# receiver_mp3.net
KiCad netlist of a schematic drawn in EAGLE
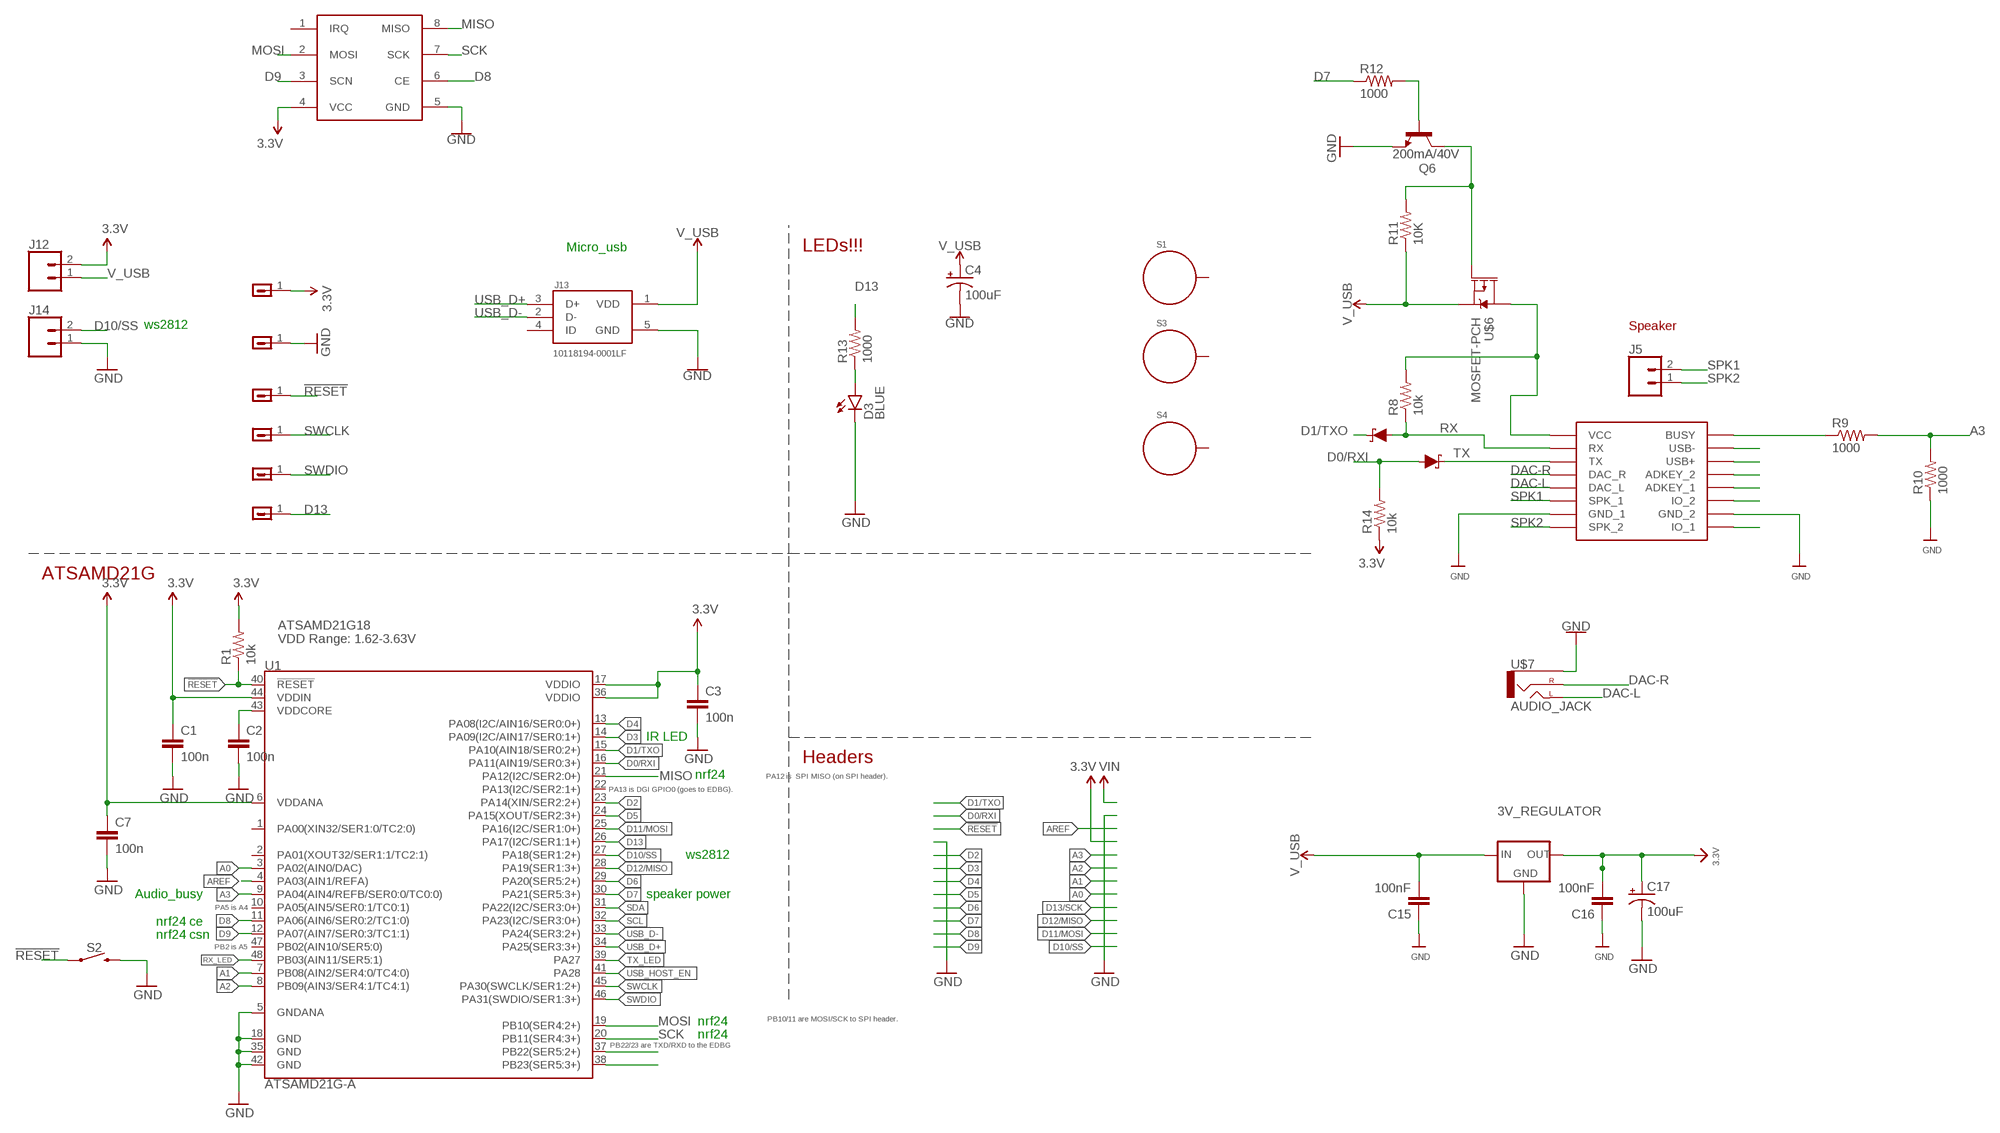
[diagram p0: schematic, sheet 1]

(export (version "E")
  (design (tool "Eeschema 10.0.6"))
  (components
    (comp (ref "3V_REGULATOR")
      (value "LDL1117_5V_REG")
      (footprint "eagle-import:SOT223")
      (libsource (lib "eagle-import") (part "LDL1117_5V_REG"))
    )
    (comp (ref "C1")
      (value "100n")
      (footprint "eagle-import:0805")
      (libsource (lib "eagle-import") (part "CAP0805"))
    )
    (comp (ref "C2")
      (value "100n")
      (footprint "eagle-import:0805")
      (libsource (lib "eagle-import") (part "CAP0805"))
    )
    (comp (ref "C3")
      (value "100n")
      (footprint "eagle-import:0805")
      (libsource (lib "eagle-import") (part "CAP0805"))
    )
    (comp (ref "C4")
      (value "100uF")
      (footprint "eagle-import:CPOL-RADIAL-2.5MM-6.5MM")
      (libsource (lib "eagle-import") (part "100UF-POLAR-RADIAL-2.5MM-25V-20%"))
    )
    (comp (ref "C7")
      (value "100n")
      (footprint "eagle-import:0805")
      (libsource (lib "eagle-import") (part "CAP0805"))
    )
    (comp (ref "C15")
      (value "100nF")
      (footprint "eagle-import:0805")
      (libsource (lib "eagle-import") (part "10UF-0805-10V-10%"))
    )
    (comp (ref "C16")
      (value "100nF")
      (footprint "eagle-import:0805")
      (libsource (lib "eagle-import") (part "10UF-0805-10V-10%"))
    )
    (comp (ref "C17")
      (value "100uF")
      (footprint "eagle-import:CPOL-RADIAL-2.5MM-6.5MM")
      (libsource (lib "eagle-import") (part "100UF-POLAR-RADIAL-2.5MM-25V-20%"))
    )
    (comp (ref "D1")
      (value "3A/40V/500mV")
      (footprint "eagle-import:SMA-DIODE")
      (libsource (lib "eagle-import") (part "DIODE-SCHOTTKY-B340A"))
    )
    (comp (ref "D3")
      (value "BLUE")
      (footprint "eagle-import:LED-1206")
      (libsource (lib "eagle-import") (part "LED-BLUE1206"))
    )
    (comp (ref "D5")
      (value "3A/40V/500mV")
      (footprint "eagle-import:SMA-DIODE")
      (libsource (lib "eagle-import") (part "DIODE-SCHOTTKY-B340A"))
    )
    (comp (ref "J5")
      (value "CONN_025MM")
      (footprint "eagle-import:SCREWTERMINAL-5MM-2")
      (libsource (lib "eagle-import") (part "CONN_025MM"))
    )
    (comp (ref "J12")
      (value "CONN_025MM")
      (footprint "eagle-import:SCREWTERMINAL-5MM-2")
      (libsource (lib "eagle-import") (part "CONN_025MM"))
    )
    (comp (ref "J13")
      (value "10118194-0001LF")
      (footprint "eagle-import:FRAMATOME_10118194-0001LF")
      (fields (field (name "MF") "Amphenol ICC"))
      (libsource (lib "eagle-import") (part "10118194-0001LF"))
    )
    (comp (ref "J14")
      (value "CONN_025MM")
      (footprint "eagle-import:SCREWTERMINAL-5MM-2")
      (libsource (lib "eagle-import") (part "CONN_025MM"))
    )
    (comp (ref "Q6")
      (value "200mA/40V")
      (footprint "eagle-import:TO-92-EZ")
      (libsource (lib "eagle-import") (part "TRANS_NPN-2N3904-EZ"))
    )
    (comp (ref "R1")
      (value "10k")
      (footprint "eagle-import:0805")
      (libsource (lib "eagle-import") (part "RESISTOR0805-RES"))
    )
    (comp (ref "R8")
      (value "10k")
      (footprint "eagle-import:0805")
      (libsource (lib "eagle-import") (part "RESISTOR0805-RES"))
    )
    (comp (ref "R9")
      (value "1000")
      (footprint "eagle-import:0805")
      (libsource (lib "eagle-import") (part "SparkFun-Passives_RESISTOR0805-RES"))
    )
    (comp (ref "R10")
      (value "1000")
      (footprint "eagle-import:0805")
      (libsource (lib "eagle-import") (part "SparkFun-Passives_RESISTOR0805-RES"))
    )
    (comp (ref "R11")
      (value "10K")
      (footprint "eagle-import:0805")
      (libsource (lib "eagle-import") (part "SparkFun-Passives_RESISTOR0805-RES"))
    )
    (comp (ref "R12")
      (value "1000")
      (footprint "eagle-import:0805")
      (libsource (lib "eagle-import") (part "SparkFun-Passives_RESISTOR0805-RES"))
    )
    (comp (ref "R13")
      (value "1000")
      (footprint "eagle-import:0805")
      (libsource (lib "eagle-import") (part "SparkFun-Passives_RESISTOR0805-RES"))
    )
    (comp (ref "R14")
      (value "10k")
      (footprint "eagle-import:0805")
      (libsource (lib "eagle-import") (part "RESISTOR0805-RES"))
    )
    (comp (ref "S1")
      (value "STANDOFF_ELECTRICAL144")
      (footprint "eagle-import:STANDOFF_ELECTRICAL_144MILL_NORMAL_SCREW")
      (libsource (lib "eagle-import") (part "STANDOFF_ELECTRICAL144"))
    )
    (comp (ref "S2")
      (value "MOMENTARY-SWITCH-SPST-PTH-6.0MM-KIT")
      (footprint "eagle-import:TACTILE_SWITCH_PTH_6.0MM_KIT")
      (libsource (lib "eagle-import") (part "MOMENTARY-SWITCH-SPST-PTH-6.0MM-KIT"))
    )
    (comp (ref "S3")
      (value "STANDOFF_ELECTRICAL144")
      (footprint "eagle-import:STANDOFF_ELECTRICAL_144MILL_NORMAL_SCREW")
      (libsource (lib "eagle-import") (part "STANDOFF_ELECTRICAL144"))
    )
    (comp (ref "S4")
      (value "STANDOFF_ELECTRICAL144")
      (footprint "eagle-import:STANDOFF_ELECTRICAL_144MILL_NORMAL_SCREW")
      (libsource (lib "eagle-import") (part "STANDOFF_ELECTRICAL144"))
    )
    (comp (ref "U$1")
      (value "DFPLAYER")
      (footprint "eagle-import:DFPLAYER")
      (libsource (lib "eagle-import") (part "DFPLAYER"))
    )
    (comp (ref "U$3")
      (value "NRF24L01")
      (footprint "eagle-import:NRF24L01")
      (libsource (lib "eagle-import") (part "NRF24L01"))
    )
    (comp (ref "U$6")
      (value "MOSFET-PCH")
      (footprint "eagle-import:DPAK")
      (libsource (lib "eagle-import") (part "MOSFET-PCH"))
    )
    (comp (ref "U$7")
      (value "AUDIO_JACK")
      (footprint "eagle-import:1_8_AUDIO_JACK")
      (libsource (lib "eagle-import") (part "AUDIO_JACK"))
    )
    (comp (ref "U$8")
      (value "CONN_011.27MM")
      (footprint "eagle-import:1X01-1.27MM")
      (libsource (lib "eagle-import") (part "CONN_011.27MM"))
    )
    (comp (ref "U$13")
      (value "CONN_011.27MM")
      (footprint "eagle-import:1X01-1.27MM")
      (libsource (lib "eagle-import") (part "CONN_011.27MM"))
    )
    (comp (ref "U$18")
      (value "CONN_011.27MM")
      (footprint "eagle-import:1X01-1.27MM")
      (libsource (lib "eagle-import") (part "CONN_011.27MM"))
    )
    (comp (ref "U$19")
      (value "CONN_011.27MM")
      (footprint "eagle-import:1X01-1.27MM")
      (libsource (lib "eagle-import") (part "CONN_011.27MM"))
    )
    (comp (ref "U$20")
      (value "CONN_011.27MM")
      (footprint "eagle-import:1X01-1.27MM")
      (libsource (lib "eagle-import") (part "CONN_011.27MM"))
    )
    (comp (ref "U$22")
      (value "CONN_011.27MM")
      (footprint "eagle-import:1X01-1.27MM")
      (libsource (lib "eagle-import") (part "CONN_011.27MM"))
    )
    (comp (ref "U1")
      (value "ATSAMD21G-A")
      (footprint "eagle-import:TQFP-48")
      (libsource (lib "eagle-import") (part "ATSAMD21G-A"))
    )
  )
  (nets
    (net (code "1") (name "/DAC-L") (class "Default")
      (node (ref "U$1") (pin "DAC_L") (pinfunction "DAC_L_DAC_L") (pintype "bidirectional"))
      (node (ref "U$7") (pin "LEFT_TIP_1") (pinfunction "LEFT_LEFT_TIP_1") (pintype "bidirectional"))
    )
    (net (code "2") (name "/DAC-R") (class "Default")
      (node (ref "U$1") (pin "DAC_R") (pinfunction "DAC_R_DAC_R") (pintype "bidirectional"))
      (node (ref "U$7") (pin "RIGHT") (pinfunction "RIGHT_RIGHT") (pintype "bidirectional"))
    )
    (net (code "3") (name "/MISO") (class "Default")
      (node (ref "U$3") (pin "8") (pinfunction "MISO_8") (pintype "bidirectional"))
      (node (ref "U1") (pin "21") (pinfunction "PA12(I2C/SER2:0+)_21") (pintype "bidirectional"))
    )
    (net (code "4") (name "/MOSI") (class "Default")
      (node (ref "U$3") (pin "2") (pinfunction "MOSI_2") (pintype "bidirectional"))
      (node (ref "U1") (pin "19") (pinfunction "PB10(SER4:2+)_19") (pintype "bidirectional"))
    )
    (net (code "5") (name "/RX") (class "Default")
      (node (ref "D1") (pin "A") (pinfunction "A_A") (pintype "passive"))
      (node (ref "R8") (pin "1") (pinfunction "1_1") (pintype "passive"))
      (node (ref "U$1") (pin "RX") (pinfunction "RX_RX") (pintype "bidirectional"))
    )
    (net (code "6") (name "/SCK") (class "Default")
      (node (ref "U$3") (pin "7") (pinfunction "SCK_7") (pintype "bidirectional"))
      (node (ref "U1") (pin "20") (pinfunction "PB11(SER4:3+)_20") (pintype "bidirectional"))
    )
    (net (code "7") (name "/SPK1") (class "Default")
      (node (ref "J5") (pin "2") (pinfunction "2_2") (pintype "passive"))
      (node (ref "U$1") (pin "SPK1") (pinfunction "SPK_1_SPK1") (pintype "bidirectional"))
    )
    (net (code "8") (name "/SPK2") (class "Default")
      (node (ref "J5") (pin "1") (pinfunction "1_1") (pintype "passive"))
      (node (ref "U$1") (pin "SPK2") (pinfunction "SPK_2_SPK2") (pintype "bidirectional"))
    )
    (net (code "9") (name "/TX") (class "Default")
      (node (ref "D5") (pin "C") (pinfunction "C_C") (pintype "passive"))
      (node (ref "U$1") (pin "TX") (pinfunction "TX_TX") (pintype "bidirectional"))
    )
    (net (code "10") (name "/~{RESET}") (class "Default")
      (node (ref "R1") (pin "1") (pinfunction "1_1") (pintype "passive"))
      (node (ref "S2") (pin "1") (pinfunction "1_1") (pintype "passive"))
      (node (ref "U$20") (pin "1") (pinfunction "1_1") (pintype "passive"))
      (node (ref "U1") (pin "40") (pinfunction "~{RESET}_40") (pintype "bidirectional"))
    )
    (net (code "11") (name "3.3V") (class "Default")
      (node (ref "3V_REGULATOR") (pin "2") (pinfunction "OUT_2") (pintype "passive"))
      (node (ref "3V_REGULATOR") (pin "4") (pinfunction "OUT_4") (pintype "passive"))
      (node (ref "C1") (pin "1") (pinfunction "1_1") (pintype "passive"))
      (node (ref "C16") (pin "2") (pinfunction "2_2") (pintype "passive"))
      (node (ref "C17") (pin "1") (pinfunction "+_1") (pintype "passive"))
      (node (ref "C3") (pin "1") (pinfunction "1_1") (pintype "passive"))
      (node (ref "C7") (pin "1") (pinfunction "1_1") (pintype "passive"))
      (node (ref "J12") (pin "2") (pinfunction "2_2") (pintype "passive"))
      (node (ref "R1") (pin "2") (pinfunction "2_2") (pintype "passive"))
      (node (ref "R14") (pin "1") (pinfunction "1_1") (pintype "passive"))
      (node (ref "U$18") (pin "1") (pinfunction "1_1") (pintype "passive"))
      (node (ref "U$3") (pin "4") (pinfunction "VCC_4") (pintype "bidirectional"))
      (node (ref "U1") (pin "17") (pinfunction "VDDIO_17") (pintype "bidirectional"))
      (node (ref "U1") (pin "36") (pinfunction "VDDIO_36") (pintype "bidirectional"))
      (node (ref "U1") (pin "44") (pinfunction "VDDIN_44") (pintype "bidirectional"))
      (node (ref "U1") (pin "6") (pinfunction "VDDANA_6") (pintype "bidirectional"))
    )
    (net (code "12") (name "A0") (class "Default")
      (node (ref "U1") (pin "3") (pinfunction "PA02(AIN0/DAC)_3") (pintype "bidirectional"))
    )
    (net (code "13") (name "A1") (class "Default")
      (node (ref "U1") (pin "7") (pinfunction "PB08(AIN2/SER4:0/TC4:0)_7") (pintype "bidirectional"))
    )
    (net (code "14") (name "A2") (class "Default")
      (node (ref "U1") (pin "8") (pinfunction "PB09(AIN3/SER4:1/TC4:1)_8") (pintype "bidirectional"))
    )
    (net (code "15") (name "A3") (class "Default")
      (node (ref "R10") (pin "2") (pinfunction "2_2") (pintype "passive"))
      (node (ref "R9") (pin "2") (pinfunction "2_2") (pintype "passive"))
      (node (ref "U1") (pin "9") (pinfunction "PA04(AIN4/REFB/SER0:0/TC0:0)_9") (pintype "bidirectional"))
    )
    (net (code "16") (name "AREF") (class "Default")
      (node (ref "U1") (pin "4") (pinfunction "PA03(AIN1/REFA)_4") (pintype "bidirectional"))
    )
    (net (code "17") (name "D0{slash}RXI") (class "Default")
      (node (ref "D5") (pin "A") (pinfunction "A_A") (pintype "passive"))
      (node (ref "R14") (pin "2") (pinfunction "2_2") (pintype "passive"))
      (node (ref "U1") (pin "16") (pinfunction "PA11(AIN19/SER0:3+)_16") (pintype "bidirectional"))
    )
    (net (code "18") (name "D1{slash}TXO") (class "Default")
      (node (ref "D1") (pin "C") (pinfunction "C_C") (pintype "passive"))
      (node (ref "U1") (pin "15") (pinfunction "PA10(AIN18/SER0:2+)_15") (pintype "bidirectional"))
    )
    (net (code "19") (name "D2") (class "Default")
      (node (ref "U1") (pin "23") (pinfunction "PA14(XIN/SER2:2+)_23") (pintype "bidirectional"))
    )
    (net (code "20") (name "D3") (class "Default")
      (node (ref "U1") (pin "14") (pinfunction "PA09(I2C/AIN17/SER0:1+)_14") (pintype "bidirectional"))
    )
    (net (code "21") (name "D4") (class "Default")
      (node (ref "U1") (pin "13") (pinfunction "PA08(I2C/AIN16/SER0:0+)_13") (pintype "bidirectional"))
    )
    (net (code "22") (name "D5") (class "Default")
      (node (ref "U1") (pin "24") (pinfunction "PA15(XOUT/SER2:3+)_24") (pintype "bidirectional"))
    )
    (net (code "23") (name "D6") (class "Default")
      (node (ref "U1") (pin "29") (pinfunction "PA20(SER5:2+)_29") (pintype "bidirectional"))
    )
    (net (code "24") (name "D7") (class "Default")
      (node (ref "R12") (pin "1") (pinfunction "1_1") (pintype "passive"))
      (node (ref "U1") (pin "30") (pinfunction "PA21(SER5:3+)_30") (pintype "bidirectional"))
    )
    (net (code "25") (name "D8") (class "Default")
      (node (ref "U$3") (pin "6") (pinfunction "CE_6") (pintype "bidirectional"))
      (node (ref "U1") (pin "11") (pinfunction "PA06(AIN6/SER0:2/TC1:0)_11") (pintype "bidirectional"))
    )
    (net (code "26") (name "D9") (class "Default")
      (node (ref "U$3") (pin "3") (pinfunction "SCN_3") (pintype "bidirectional"))
      (node (ref "U1") (pin "12") (pinfunction "PA07(AIN7/SER0:3/TC1:1)_12") (pintype "bidirectional"))
    )
    (net (code "27") (name "D10{slash}SS") (class "Default")
      (node (ref "J14") (pin "2") (pinfunction "2_2") (pintype "passive"))
      (node (ref "U1") (pin "27") (pinfunction "PA18(SER1:2+)_27") (pintype "bidirectional"))
    )
    (net (code "28") (name "D11{slash}MOSI") (class "Default")
      (node (ref "U1") (pin "25") (pinfunction "PA16(I2C/SER1:0+)_25") (pintype "bidirectional"))
    )
    (net (code "29") (name "D12{slash}MISO") (class "Default")
      (node (ref "U1") (pin "28") (pinfunction "PA19(SER1:3+)_28") (pintype "bidirectional"))
    )
    (net (code "30") (name "D13") (class "Default")
      (node (ref "R13") (pin "2") (pinfunction "2_2") (pintype "passive"))
      (node (ref "U$8") (pin "1") (pinfunction "1_1") (pintype "passive"))
      (node (ref "U1") (pin "26") (pinfunction "PA17(I2C/SER1:1+)_26") (pintype "bidirectional"))
    )
    (net (code "32") (name "GND") (class "Default")
      (node (ref "3V_REGULATOR") (pin "1") (pinfunction "GND_1") (pintype "input"))
      (node (ref "C1") (pin "2") (pinfunction "2_2") (pintype "passive"))
      (node (ref "C15") (pin "1") (pinfunction "1_1") (pintype "passive"))
      (node (ref "C16") (pin "1") (pinfunction "1_1") (pintype "passive"))
      (node (ref "C17") (pin "2") (pinfunction "-_2") (pintype "passive"))
      (node (ref "C2") (pin "2") (pinfunction "2_2") (pintype "passive"))
      (node (ref "C3") (pin "2") (pinfunction "2_2") (pintype "passive"))
      (node (ref "C4") (pin "2") (pinfunction "-_2") (pintype "passive"))
      (node (ref "C7") (pin "2") (pinfunction "2_2") (pintype "passive"))
      (node (ref "D3") (pin "C") (pinfunction "C_C") (pintype "passive"))
      (node (ref "J13") (pin "5") (pinfunction "GND_5") (pintype "power_in"))
      (node (ref "J14") (pin "1") (pinfunction "1_1") (pintype "passive"))
      (node (ref "Q6") (pin "1") (pinfunction "E_1") (pintype "passive"))
      (node (ref "R10") (pin "1") (pinfunction "1_1") (pintype "passive"))
      (node (ref "S2") (pin "3") (pinfunction "2_3") (pintype "passive"))
      (node (ref "U$1") (pin "GND_1") (pinfunction "GND_1_GND_1") (pintype "bidirectional"))
      (node (ref "U$1") (pin "GND_2") (pinfunction "GND_2_GND_2") (pintype "bidirectional"))
      (node (ref "U$13") (pin "1") (pinfunction "1_1") (pintype "passive"))
      (node (ref "U$3") (pin "5") (pinfunction "GND_5") (pintype "bidirectional"))
      (node (ref "U$7") (pin "GND") (pinfunction "SLEEVE_GND") (pintype "bidirectional"))
      (node (ref "U1") (pin "18") (pinfunction "GND_18") (pintype "bidirectional"))
      (node (ref "U1") (pin "35") (pinfunction "GND_35") (pintype "bidirectional"))
      (node (ref "U1") (pin "42") (pinfunction "GND_42") (pintype "bidirectional"))
      (node (ref "U1") (pin "5") (pinfunction "GNDANA_5") (pintype "bidirectional"))
    )
    (net (code "33") (name "Net-(D3-PadA)") (class "Default")
      (node (ref "D3") (pin "A") (pinfunction "A_A") (pintype "passive"))
      (node (ref "R13") (pin "1") (pinfunction "1_1") (pintype "passive"))
    )
    (net (code "34") (name "Net-(Q6-B)") (class "Default")
      (node (ref "Q6") (pin "2") (pinfunction "B_2") (pintype "passive"))
      (node (ref "R12") (pin "2") (pinfunction "2_2") (pintype "passive"))
    )
    (net (code "35") (name "Net-(Q6-C)") (class "Default")
      (node (ref "Q6") (pin "3") (pinfunction "C_3") (pintype "passive"))
      (node (ref "R11") (pin "2") (pinfunction "2_2") (pintype "passive"))
      (node (ref "U$6") (pin "1") (pinfunction "G_1") (pintype "bidirectional"))
    )
    (net (code "36") (name "Net-(R9-Pad1)") (class "Default")
      (node (ref "R9") (pin "1") (pinfunction "1_1") (pintype "passive"))
      (node (ref "U$1") (pin "BUSY") (pinfunction "BUSY_BUSY") (pintype "bidirectional"))
    )
    (net (code "37") (name "Net-(U$6-D)") (class "Default")
      (node (ref "R8") (pin "2") (pinfunction "2_2") (pintype "passive"))
      (node (ref "U$1") (pin "VCC") (pinfunction "VCC_VCC") (pintype "bidirectional"))
      (node (ref "U$6") (pin "4") (pinfunction "D_4") (pintype "bidirectional"))
    )
    (net (code "38") (name "Net-(U1-VDDCORE)") (class "Default")
      (node (ref "C2") (pin "1") (pinfunction "1_1") (pintype "passive"))
      (node (ref "U1") (pin "43") (pinfunction "VDDCORE_43") (pintype "bidirectional"))
    )
    (net (code "39") (name "RX_LED") (class "Default")
      (node (ref "U1") (pin "48") (pinfunction "PB03(AIN11/SER5:1)_48") (pintype "bidirectional"))
    )
    (net (code "40") (name "SCL") (class "Default")
      (node (ref "U1") (pin "32") (pinfunction "PA23(I2C/SER3:0+)_32") (pintype "bidirectional"))
    )
    (net (code "41") (name "SDA") (class "Default")
      (node (ref "U1") (pin "31") (pinfunction "PA22(I2C/SER3:0+)_31") (pintype "bidirectional"))
    )
    (net (code "42") (name "SWCLK") (class "Default")
      (node (ref "U$22") (pin "1") (pinfunction "1_1") (pintype "passive"))
      (node (ref "U1") (pin "45") (pinfunction "PA30(SWCLK/SER1:2+)_45") (pintype "bidirectional"))
    )
    (net (code "43") (name "SWDIO") (class "Default")
      (node (ref "U$19") (pin "1") (pinfunction "1_1") (pintype "passive"))
      (node (ref "U1") (pin "46") (pinfunction "PA31(SWDIO/SER1:3+)_46") (pintype "bidirectional"))
    )
    (net (code "44") (name "TX_LED") (class "Default")
      (node (ref "U1") (pin "39") (pinfunction "PA27_39") (pintype "bidirectional"))
    )
    (net (code "45") (name "USB_D+") (class "Default")
      (node (ref "J13") (pin "3") (pinfunction "D+_3") (pintype "bidirectional"))
      (node (ref "U1") (pin "34") (pinfunction "PA25(SER3:3+)_34") (pintype "bidirectional"))
    )
    (net (code "46") (name "USB_D-") (class "Default")
      (node (ref "J13") (pin "2") (pinfunction "D-_2") (pintype "bidirectional"))
      (node (ref "U1") (pin "33") (pinfunction "PA24(SER3:2+)_33") (pintype "bidirectional"))
    )
    (net (code "47") (name "USB_HOST_EN") (class "Default")
      (node (ref "U1") (pin "41") (pinfunction "PA28_41") (pintype "bidirectional"))
    )
    (net (code "49") (name "V_USB") (class "Default")
      (node (ref "3V_REGULATOR") (pin "3") (pinfunction "IN_3") (pintype "input"))
      (node (ref "C15") (pin "2") (pinfunction "2_2") (pintype "passive"))
      (node (ref "C4") (pin "1") (pinfunction "+_1") (pintype "passive"))
      (node (ref "J12") (pin "1") (pinfunction "1_1") (pintype "passive"))
      (node (ref "J13") (pin "1") (pinfunction "VDD_1") (pintype "power_in"))
      (node (ref "R11") (pin "1") (pinfunction "1_1") (pintype "passive"))
      (node (ref "U$6") (pin "3") (pinfunction "S_3") (pintype "bidirectional"))
    )
    (net (code "50") (name "unconnected-(J13-ID-Pad4)") (class "Default")
      (node (ref "J13") (pin "4") (pinfunction "ID_4") (pintype "passive"))
    )
    (net (code "51") (name "unconnected-(S1-P$1-PadP1)") (class "Default")
      (node (ref "S1") (pin "P1") (pinfunction "P$1_P1") (pintype "bidirectional"))
    )
    (net (code "52") (name "unconnected-(S3-P$1-PadP1)") (class "Default")
      (node (ref "S3") (pin "P1") (pinfunction "P$1_P1") (pintype "bidirectional"))
    )
    (net (code "53") (name "unconnected-(S4-P$1-PadP1)") (class "Default")
      (node (ref "S4") (pin "P1") (pinfunction "P$1_P1") (pintype "bidirectional"))
    )
    (net (code "54") (name "unconnected-(U$1-ADKEY_1-PadADKEY1)") (class "Default")
      (node (ref "U$1") (pin "ADKEY1") (pinfunction "ADKEY_1_ADKEY1") (pintype "bidirectional"))
    )
    (net (code "55") (name "unconnected-(U$1-ADKEY_2-PadADKEY2)") (class "Default")
      (node (ref "U$1") (pin "ADKEY2") (pinfunction "ADKEY_2_ADKEY2") (pintype "bidirectional"))
    )
    (net (code "56") (name "unconnected-(U$1-IO_1-PadIO1)") (class "Default")
      (node (ref "U$1") (pin "IO1") (pinfunction "IO_1_IO1") (pintype "bidirectional"))
    )
    (net (code "57") (name "unconnected-(U$1-IO_2-PadIO2)") (class "Default")
      (node (ref "U$1") (pin "IO2") (pinfunction "IO_2_IO2") (pintype "bidirectional"))
    )
    (net (code "58") (name "unconnected-(U$1-PadUSB+)") (class "Default")
      (node (ref "U$1") (pin "USB+") (pinfunction "USB+_USB+") (pintype "bidirectional"))
    )
    (net (code "59") (name "unconnected-(U$1-PadUSB-)") (class "Default")
      (node (ref "U$1") (pin "USB-") (pinfunction "USB-_USB-") (pintype "bidirectional"))
    )
    (net (code "60") (name "unconnected-(U$3-IRQ-Pad1)") (class "Default")
      (node (ref "U$3") (pin "1") (pinfunction "IRQ_1") (pintype "bidirectional"))
    )
    (net (code "61") (name "unconnected-(U1-PA00(XIN32{slash}SER1:0{slash}TC2:0)-Pad1)") (class "Default")
      (node (ref "U1") (pin "1") (pinfunction "PA00(XIN32/SER1:0/TC2:0)_1") (pintype "bidirectional"))
    )
    (net (code "62") (name "unconnected-(U1-PA01(XOUT32{slash}SER1:1{slash}TC2:1)-Pad2)") (class "Default")
      (node (ref "U1") (pin "2") (pinfunction "PA01(XOUT32/SER1:1/TC2:1)_2") (pintype "bidirectional"))
    )
    (net (code "63") (name "unconnected-(U1-PA05(AIN5{slash}SER0:1{slash}TC0:1)-Pad10)") (class "Default")
      (node (ref "U1") (pin "10") (pinfunction "PA05(AIN5/SER0:1/TC0:1)_10") (pintype "bidirectional"))
    )
    (net (code "64") (name "unconnected-(U1-PA13(I2C{slash}SER2:1+)-Pad22)") (class "Default")
      (node (ref "U1") (pin "22") (pinfunction "PA13(I2C/SER2:1+)_22") (pintype "bidirectional"))
    )
    (net (code "65") (name "unconnected-(U1-PB02(AIN10{slash}SER5:0)-Pad47)") (class "Default")
      (node (ref "U1") (pin "47") (pinfunction "PB02(AIN10/SER5:0)_47") (pintype "bidirectional"))
    )
    (net (code "66") (name "unconnected-(U1-PB22(SER5:2+)-Pad37)") (class "Default")
      (node (ref "U1") (pin "37") (pinfunction "PB22(SER5:2+)_37") (pintype "bidirectional"))
    )
    (net (code "67") (name "unconnected-(U1-PB23(SER5:3+)-Pad38)") (class "Default")
      (node (ref "U1") (pin "38") (pinfunction "PB23(SER5:3+)_38") (pintype "bidirectional"))
    )
  )
)
